# Bluetooth.net
KiCad netlist of a schematic drawn in Altium Designer
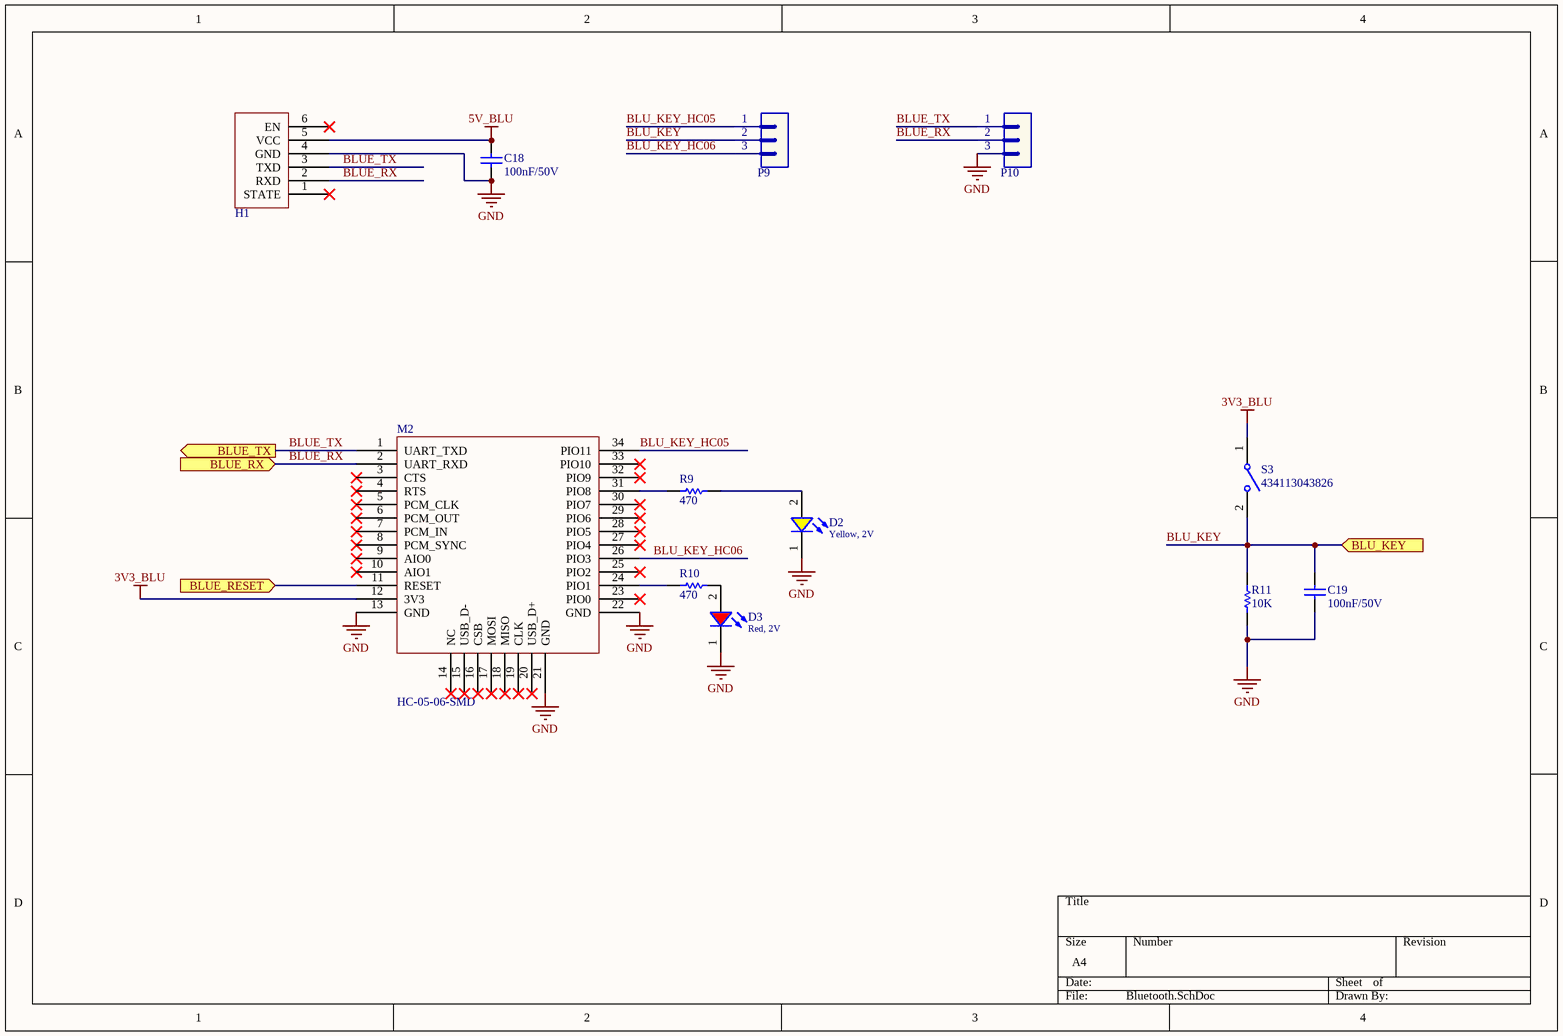
[diagram p0: Bluetooth.SchDoc]

(export (version "E")
  (design (tool "Eeschema 10.0.6"))
  (components
    (comp (ref "C18")
      (value "100nF/50V")
      (footprint "CAP-SM-0805")
      (description "CAP CER 0.1UF 50V Y5V 0805")
      (fields
        (field (name "MANUFACTURER") "Samsung Electro-Mechanics")
        (field (name "MANUFACTURER PART NUMBER") "CL21F104ZBCNNNC")
      )
      (libsource (lib "Capacitor") (part "Cap-100nF-50V-0805"))
    )
    (comp (ref "C19")
      (value "100nF/50V")
      (footprint "CAP-SM-0805")
      (description "CAP CER 0.1UF 50V Y5V 0805")
      (fields
        (field (name "MANUFACTURER") "Samsung Electro-Mechanics")
        (field (name "MANUFACTURER PART NUMBER") "CL21F104ZBCNNNC")
      )
      (libsource (lib "Capacitor") (part "Cap-100nF-50V-0805"))
    )
    (comp (ref "D2")
      (value "Yellow, 2V")
      (footprint "WL-SMCW_0805")
      (description "WL-SMCW SMT Mono-color Chip LED Waterclear, size 0805, Yellow, 2V, 140deg")
      (fields (field (name "PART NUMBER") "150080YS75000") (field (name "PUBLISHER") "Wurth Elektronik"))
      (libsource (lib "LED_GREEN") (part "150080YS75000"))
    )
    (comp (ref "D3")
      (value "Red, 2V")
      (footprint "WL-SMCW_0805")
      (description "WL-SMCW SMT Mono-color Chip LED Waterclear, size 0805, Red, 2V, 140deg")
      (fields (field (name "PART NUMBER") "150080RS75000") (field (name "PUBLISHER") "Wurth Elektronik"))
      (libsource (lib "LED_GREEN") (part "150080RS75000"))
    )
    (comp (ref "H1")
      (value "HC-05-06-TH")
      (footprint "HC-05-06-TH")
      (fields (field (name "LOCAL SUPPLIER PART NUMBER") "HS000882"))
      (libsource (lib "xecanbang") (part "HC-05-06-TH"))
    )
    (comp (ref "M2")
      (value "HC-05-06-SMD")
      (footprint "HC-05-06-SMD")
      (fields (field (name "LOCAL SUPPLIER PART NUMBER") "HS000881"))
      (libsource (lib "xecanbang") (part "HC-05-06-SMD"))
    )
    (comp (ref "P9")
      (value "Header 3")
      (footprint "JP3")
      (description "Header, 3-Pin")
      (fields (field (name "PUBLISHER") "Altium Limited"))
      (libsource (lib "Header-connector") (part "Header 3"))
    )
    (comp (ref "P10")
      (value "Header 3")
      (footprint "JP3")
      (description "Header, 3-Pin")
      (fields (field (name "PUBLISHER") "Altium Limited"))
      (libsource (lib "Header-connector") (part "Header 3"))
    )
    (comp (ref "R9")
      (value "470")
      (footprint "Resistor:RES-SM-0805")
      (description "RES 470 OHM JUMPER 0805")
      (fields
        (field (name "MANUFACTURER") "YAG6006CT-ND")
        (field (name "MANUFACTURER PART NUMBER") "PE0805FRF7W0R047L")
      )
      (libsource (lib "Resistor") (part "Res-470-0805"))
    )
    (comp (ref "R10")
      (value "470")
      (footprint "Resistor:RES-SM-0805")
      (description "RES 470 OHM JUMPER 0805")
      (fields
        (field (name "MANUFACTURER") "YAG6006CT-ND")
        (field (name "MANUFACTURER PART NUMBER") "PE0805FRF7W0R047L")
      )
      (libsource (lib "Resistor") (part "Res-470-0805"))
    )
    (comp (ref "R11")
      (value "10K")
      (footprint "Resistor:RES-SM-0805")
      (description "RES 10K OHM 1% 1/4W 0805")
      (fields
        (field (name "MANUFACTURER") "Stackpole Electronics Inc")
        (field (name "MANUFACTURER PART NUMBER") "RNCP0805FTD10K0")
      )
      (libsource (lib "Resistor") (part "Res-10k-0805"))
    )
    (comp (ref "S3")
      (value "434113043826")
      (footprint "434113043826")
      (description "WS-TASV J-Bend SMT Tact Switch 6x3.5mm, height 4.3mm, 260gf")
      (fields (field (name "PUBLISHER") "Wurth Elektronik"))
      (libsource (lib "434123043816") (part "434113043826"))
    )
  )
  (nets
    (net (code "1") (name "/BLUE_RESET") (class "Default")
      (node (ref "M2") (pin "11") (pinfunction "RESET_11") (pintype "passive"))
    )
    (net (code "2") (name "/BLUE_RX") (class "Default")
      (node (ref "H1") (pin "2") (pinfunction "RXD_2") (pintype "passive"))
      (node (ref "M2") (pin "2") (pinfunction "UART_RXD_2") (pintype "passive"))
      (node (ref "P10") (pin "2") (pinfunction "2_2") (pintype "passive"))
    )
    (net (code "3") (name "/BLUE_TX") (class "Default")
      (node (ref "H1") (pin "3") (pinfunction "TXD_3") (pintype "passive"))
      (node (ref "M2") (pin "1") (pinfunction "UART_TXD_1") (pintype "passive"))
      (node (ref "P10") (pin "1") (pinfunction "1_1") (pintype "passive"))
    )
    (net (code "4") (name "/BLU_KEY") (class "Default")
      (node (ref "C19") (pin "1") (pinfunction "1_1") (pintype "passive"))
      (node (ref "P9") (pin "2") (pinfunction "2_2") (pintype "passive"))
      (node (ref "R11") (pin "2") (pinfunction "2_2") (pintype "passive"))
      (node (ref "S3") (pin "2") (pinfunction "2_2") (pintype "passive"))
    )
    (net (code "5") (name "/BLU_KEY_HC05") (class "Default")
      (node (ref "M2") (pin "34") (pinfunction "PIO11_34") (pintype "passive"))
      (node (ref "P9") (pin "1") (pinfunction "1_1") (pintype "passive"))
    )
    (net (code "6") (name "/BLU_KEY_HC06") (class "Default")
      (node (ref "M2") (pin "26") (pinfunction "PIO3_26") (pintype "passive"))
      (node (ref "P9") (pin "3") (pinfunction "3_3") (pintype "passive"))
    )
    (net (code "7") (name "3V3_BLU") (class "Default")
      (node (ref "M2") (pin "12") (pinfunction "3V3_12") (pintype "passive"))
      (node (ref "S3") (pin "1") (pinfunction "1_1") (pintype "passive"))
    )
    (net (code "8") (name "5V_BLU") (class "Default")
      (node (ref "C18") (pin "2") (pinfunction "2_2") (pintype "passive"))
      (node (ref "H1") (pin "5") (pinfunction "VCC_5") (pintype "passive"))
    )
    (net (code "9") (name "GND") (class "Default")
      (node (ref "C18") (pin "1") (pinfunction "1_1") (pintype "passive"))
      (node (ref "C19") (pin "2") (pinfunction "2_2") (pintype "passive"))
      (node (ref "D2") (pin "1") (pinfunction "K_1") (pintype "passive"))
      (node (ref "D3") (pin "1") (pinfunction "K_1") (pintype "passive"))
      (node (ref "H1") (pin "4") (pinfunction "GND_4") (pintype "passive"))
      (node (ref "M2") (pin "13") (pinfunction "GND_13") (pintype "passive"))
      (node (ref "M2") (pin "21") (pinfunction "GND_21") (pintype "passive"))
      (node (ref "M2") (pin "22") (pinfunction "GND_22") (pintype "passive"))
      (node (ref "P10") (pin "3") (pinfunction "3_3") (pintype "passive"))
      (node (ref "R11") (pin "1") (pinfunction "1_1") (pintype "passive"))
    )
    (net (code "10") (name "Net-(D2-A)") (class "Default")
      (node (ref "D2") (pin "2") (pinfunction "A_2") (pintype "passive"))
      (node (ref "R9") (pin "2") (pinfunction "2_2") (pintype "passive"))
    )
    (net (code "11") (name "Net-(D3-A)") (class "Default")
      (node (ref "D3") (pin "2") (pinfunction "A_2") (pintype "passive"))
      (node (ref "R10") (pin "2") (pinfunction "2_2") (pintype "passive"))
    )
    (net (code "12") (name "Net-(M2-PIO1)") (class "Default")
      (node (ref "M2") (pin "24") (pinfunction "PIO1_24") (pintype "passive"))
      (node (ref "R10") (pin "1") (pinfunction "1_1") (pintype "passive"))
    )
    (net (code "13") (name "Net-(M2-PIO8)") (class "Default")
      (node (ref "M2") (pin "31") (pinfunction "PIO8_31") (pintype "passive"))
      (node (ref "R9") (pin "1") (pinfunction "1_1") (pintype "passive"))
    )
    (net (code "14") (name "unconnected-(H1-EN-Pad6)") (class "Default")
      (node (ref "H1") (pin "6") (pinfunction "EN_6") (pintype "passive+no_connect"))
    )
    (net (code "15") (name "unconnected-(H1-STATE-Pad1)") (class "Default")
      (node (ref "H1") (pin "1") (pinfunction "STATE_1") (pintype "passive+no_connect"))
    )
    (net (code "16") (name "unconnected-(M2-AIO0-Pad9)") (class "Default")
      (node (ref "M2") (pin "9") (pinfunction "AIO0_9") (pintype "passive+no_connect"))
    )
    (net (code "17") (name "unconnected-(M2-AIO1-Pad10)") (class "Default")
      (node (ref "M2") (pin "10") (pinfunction "AIO1_10") (pintype "passive+no_connect"))
    )
    (net (code "18") (name "unconnected-(M2-CLK-Pad19)") (class "Default")
      (node (ref "M2") (pin "19") (pinfunction "CLK_19") (pintype "passive+no_connect"))
    )
    (net (code "19") (name "unconnected-(M2-CSB-Pad16)") (class "Default")
      (node (ref "M2") (pin "16") (pinfunction "CSB_16") (pintype "passive+no_connect"))
    )
    (net (code "20") (name "unconnected-(M2-CTS-Pad3)") (class "Default")
      (node (ref "M2") (pin "3") (pinfunction "CTS_3") (pintype "passive+no_connect"))
    )
    (net (code "21") (name "unconnected-(M2-MISO-Pad18)") (class "Default")
      (node (ref "M2") (pin "18") (pinfunction "MISO_18") (pintype "passive+no_connect"))
    )
    (net (code "22") (name "unconnected-(M2-MOSI-Pad17)") (class "Default")
      (node (ref "M2") (pin "17") (pinfunction "MOSI_17") (pintype "passive+no_connect"))
    )
    (net (code "23") (name "unconnected-(M2-NC-Pad14)") (class "Default")
      (node (ref "M2") (pin "14") (pinfunction "NC_14") (pintype "passive+no_connect"))
    )
    (net (code "24") (name "unconnected-(M2-PCM_CLK-Pad5)") (class "Default")
      (node (ref "M2") (pin "5") (pinfunction "PCM_CLK_5") (pintype "passive+no_connect"))
    )
    (net (code "25") (name "unconnected-(M2-PCM_IN-Pad7)") (class "Default")
      (node (ref "M2") (pin "7") (pinfunction "PCM_IN_7") (pintype "passive+no_connect"))
    )
    (net (code "26") (name "unconnected-(M2-PCM_OUT-Pad6)") (class "Default")
      (node (ref "M2") (pin "6") (pinfunction "PCM_OUT_6") (pintype "passive+no_connect"))
    )
    (net (code "27") (name "unconnected-(M2-PCM_SYNC-Pad8)") (class "Default")
      (node (ref "M2") (pin "8") (pinfunction "PCM_SYNC_8") (pintype "passive+no_connect"))
    )
    (net (code "28") (name "unconnected-(M2-PIO0-Pad23)") (class "Default")
      (node (ref "M2") (pin "23") (pinfunction "PIO0_23") (pintype "passive+no_connect"))
    )
    (net (code "29") (name "unconnected-(M2-PIO2-Pad25)") (class "Default")
      (node (ref "M2") (pin "25") (pinfunction "PIO2_25") (pintype "passive+no_connect"))
    )
    (net (code "30") (name "unconnected-(M2-PIO4-Pad27)") (class "Default")
      (node (ref "M2") (pin "27") (pinfunction "PIO4_27") (pintype "passive+no_connect"))
    )
    (net (code "31") (name "unconnected-(M2-PIO5-Pad28)") (class "Default")
      (node (ref "M2") (pin "28") (pinfunction "PIO5_28") (pintype "passive+no_connect"))
    )
    (net (code "32") (name "unconnected-(M2-PIO6-Pad29)") (class "Default")
      (node (ref "M2") (pin "29") (pinfunction "PIO6_29") (pintype "passive+no_connect"))
    )
    (net (code "33") (name "unconnected-(M2-PIO7-Pad30)") (class "Default")
      (node (ref "M2") (pin "30") (pinfunction "PIO7_30") (pintype "passive+no_connect"))
    )
    (net (code "34") (name "unconnected-(M2-PIO9-Pad32)") (class "Default")
      (node (ref "M2") (pin "32") (pinfunction "PIO9_32") (pintype "passive+no_connect"))
    )
    (net (code "35") (name "unconnected-(M2-PIO10-Pad33)") (class "Default")
      (node (ref "M2") (pin "33") (pinfunction "PIO10_33") (pintype "passive+no_connect"))
    )
    (net (code "36") (name "unconnected-(M2-RTS-Pad4)") (class "Default")
      (node (ref "M2") (pin "4") (pinfunction "RTS_4") (pintype "passive+no_connect"))
    )
    (net (code "37") (name "unconnected-(M2-USB_D+-Pad20)") (class "Default")
      (node (ref "M2") (pin "20") (pinfunction "USB_D+_20") (pintype "passive+no_connect"))
    )
    (net (code "38") (name "unconnected-(M2-USB_D--Pad15)") (class "Default")
      (node (ref "M2") (pin "15") (pinfunction "USB_D-_15") (pintype "passive+no_connect"))
    )
  )
)
